# Connecteur_Nucleo.net
KiCad netlist of a schematic drawn in Altium Designer
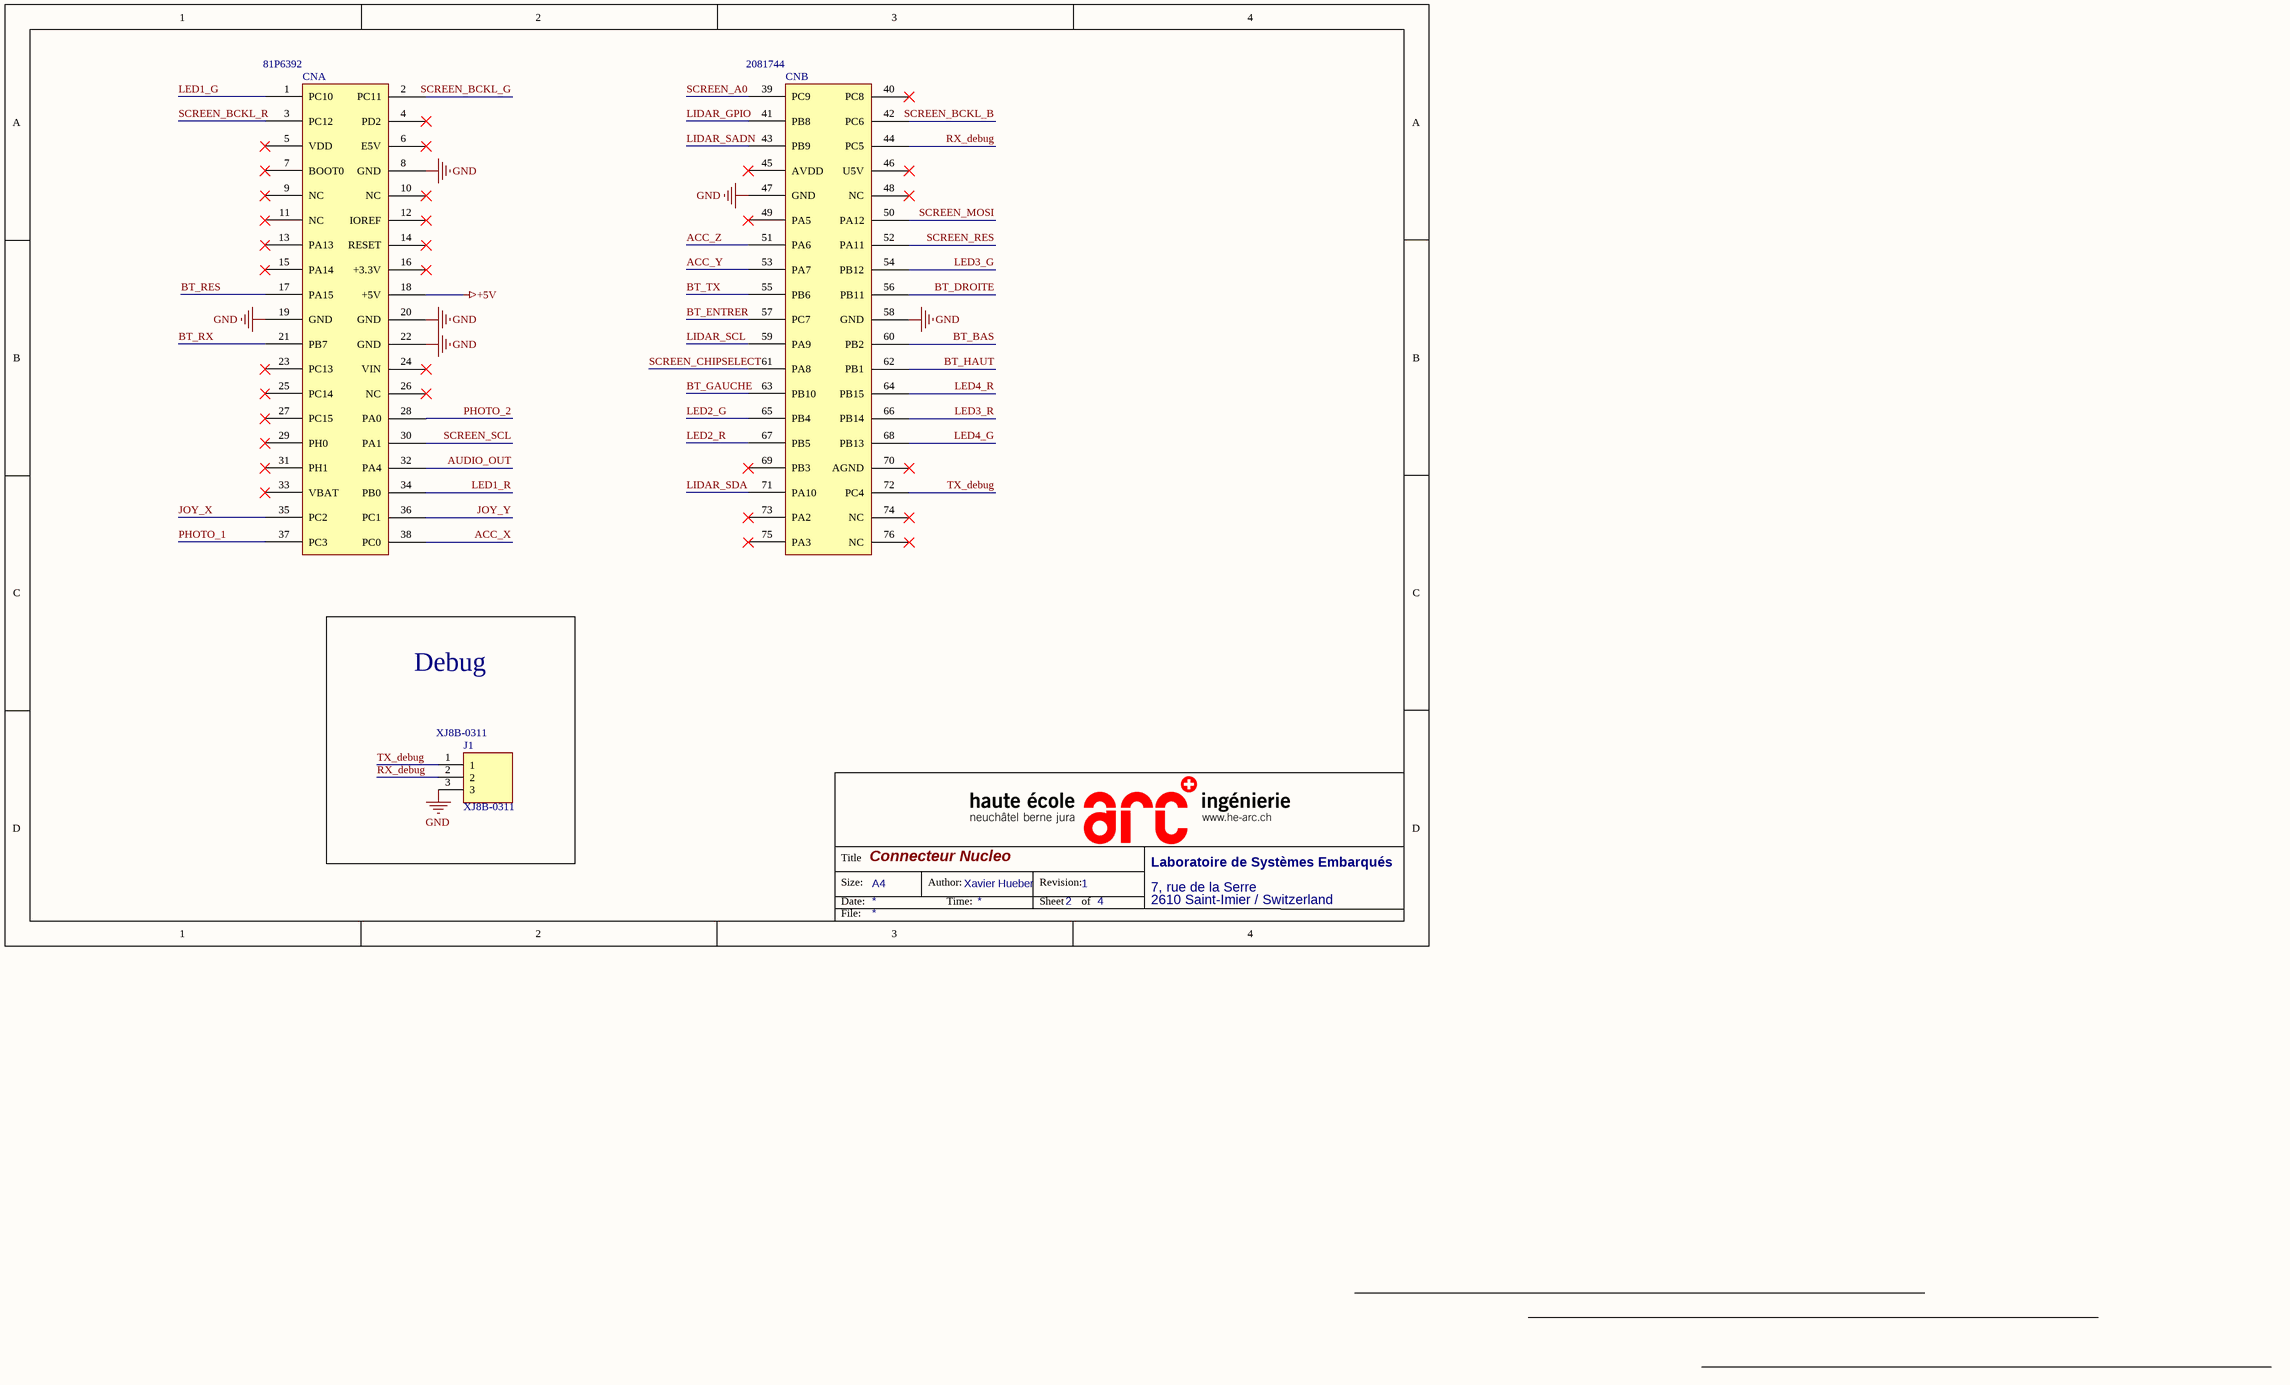
[diagram p0: Connecteur_Nucleo.SchDoc]

(export (version "E")
  (design (tool "Eeschema 10.0.6"))
  (components
    (comp (ref "CN")
      (value "~")
      (footprint "Nucleo-conn-SMD - sans 3D")
      (description "Headers & Wire Housings Surface Mount PCB Socket Strips, 0.100 pitch")
      (fields (field (name "SUPPLIER PART NUMBER 1") "81P6392"))
      (libsource (lib "MesComposants") (part "CN1"))
    )
    (comp (ref "J1")
      (value "XJ8B-0311")
      (footprint "SamacSys:HDRV3W64P0X254_1X3_760X250X580P")
      (description "Conn Unshrouded Header PL 3 POS 2.54mm Solder ST Top Entry Thru-Hole")
      (fields (field (name "SUPPLIER PART NUMBER 1") "XJ8B-0311"))
      (libsource (lib "*") (part "XJ8B-0311"))
    )
  )
  (nets
    (net (code "1") (name "+5V") (class "Default")
      (node (ref "CN") (pin "18") (pinfunction "+5V_18") (pintype "passive"))
    )
    (net (code "2") (name "/ACC_X") (class "Default")
      (node (ref "CN") (pin "38") (pinfunction "PC0_38") (pintype "passive"))
    )
    (net (code "3") (name "/ACC_Y") (class "Default")
      (node (ref "CN") (pin "53") (pinfunction "PA7_53") (pintype "passive"))
    )
    (net (code "4") (name "/ACC_Z") (class "Default")
      (node (ref "CN") (pin "51") (pinfunction "PA6_51") (pintype "passive"))
    )
    (net (code "5") (name "/AUDIO_OUT") (class "Default")
      (node (ref "CN") (pin "32") (pinfunction "PA4_32") (pintype "passive"))
    )
    (net (code "6") (name "/BT_BAS") (class "Default")
      (node (ref "CN") (pin "60") (pinfunction "PB2_60") (pintype "passive"))
    )
    (net (code "7") (name "/BT_DROITE") (class "Default")
      (node (ref "CN") (pin "56") (pinfunction "PB11_56") (pintype "passive"))
    )
    (net (code "8") (name "/BT_ENTRER") (class "Default")
      (node (ref "CN") (pin "57") (pinfunction "PC7_57") (pintype "passive"))
    )
    (net (code "9") (name "/BT_GAUCHE") (class "Default")
      (node (ref "CN") (pin "63") (pinfunction "PB10_63") (pintype "passive"))
    )
    (net (code "10") (name "/BT_HAUT") (class "Default")
      (node (ref "CN") (pin "62") (pinfunction "PB1_62") (pintype "passive"))
    )
    (net (code "11") (name "/BT_RES") (class "Default")
      (node (ref "CN") (pin "17") (pinfunction "PA15_17") (pintype "passive"))
    )
    (net (code "12") (name "/BT_RX") (class "Default")
      (node (ref "CN") (pin "21") (pinfunction "PB7_21") (pintype "passive"))
    )
    (net (code "13") (name "/BT_TX") (class "Default")
      (node (ref "CN") (pin "55") (pinfunction "PB6_55") (pintype "passive"))
    )
    (net (code "14") (name "/JOY_X") (class "Default")
      (node (ref "CN") (pin "35") (pinfunction "PC2_35") (pintype "passive"))
    )
    (net (code "15") (name "/JOY_Y") (class "Default")
      (node (ref "CN") (pin "36") (pinfunction "PC1_36") (pintype "passive"))
    )
    (net (code "16") (name "/LED1_G") (class "Default")
      (node (ref "CN") (pin "1") (pinfunction "PC10_1") (pintype "passive"))
    )
    (net (code "17") (name "/LED1_R") (class "Default")
      (node (ref "CN") (pin "34") (pinfunction "PB0_34") (pintype "passive"))
    )
    (net (code "18") (name "/LED2_G") (class "Default")
      (node (ref "CN") (pin "65") (pinfunction "PB4_65") (pintype "passive"))
    )
    (net (code "19") (name "/LED2_R") (class "Default")
      (node (ref "CN") (pin "67") (pinfunction "PB5_67") (pintype "passive"))
    )
    (net (code "20") (name "/LED3_G") (class "Default")
      (node (ref "CN") (pin "54") (pinfunction "PB12_54") (pintype "passive"))
    )
    (net (code "21") (name "/LED3_R") (class "Default")
      (node (ref "CN") (pin "66") (pinfunction "PB14_66") (pintype "passive"))
    )
    (net (code "22") (name "/LED4_G") (class "Default")
      (node (ref "CN") (pin "68") (pinfunction "PB13_68") (pintype "passive"))
    )
    (net (code "23") (name "/LED4_R") (class "Default")
      (node (ref "CN") (pin "64") (pinfunction "PB15_64") (pintype "passive"))
    )
    (net (code "24") (name "/LIDAR_GPIO") (class "Default")
      (node (ref "CN") (pin "41") (pinfunction "PB8_41") (pintype "passive"))
    )
    (net (code "25") (name "/LIDAR_SADN") (class "Default")
      (node (ref "CN") (pin "43") (pinfunction "PB9_43") (pintype "passive"))
    )
    (net (code "26") (name "/LIDAR_SCL") (class "Default")
      (node (ref "CN") (pin "59") (pinfunction "PA9_59") (pintype "passive"))
    )
    (net (code "27") (name "/LIDAR_SDA") (class "Default")
      (node (ref "CN") (pin "71") (pinfunction "PA10_71") (pintype "passive"))
    )
    (net (code "28") (name "/PHOTO_1") (class "Default")
      (node (ref "CN") (pin "37") (pinfunction "PC3_37") (pintype "passive"))
    )
    (net (code "29") (name "/PHOTO_2") (class "Default")
      (node (ref "CN") (pin "28") (pinfunction "PA0_28") (pintype "passive"))
    )
    (net (code "30") (name "/RX_debug") (class "Default")
      (node (ref "CN") (pin "44") (pinfunction "PC5_44") (pintype "passive"))
      (node (ref "J1") (pin "2") (pinfunction "2_2") (pintype "passive"))
    )
    (net (code "31") (name "/SCREEN_A0") (class "Default")
      (node (ref "CN") (pin "39") (pinfunction "PC9_39") (pintype "passive"))
    )
    (net (code "32") (name "/SCREEN_BCKL_B") (class "Default")
      (node (ref "CN") (pin "42") (pinfunction "PC6_42") (pintype "passive"))
    )
    (net (code "33") (name "/SCREEN_BCKL_G") (class "Default")
      (node (ref "CN") (pin "2") (pinfunction "PC11_2") (pintype "passive"))
    )
    (net (code "34") (name "/SCREEN_BCKL_R") (class "Default")
      (node (ref "CN") (pin "3") (pinfunction "PC12_3") (pintype "passive"))
    )
    (net (code "35") (name "/SCREEN_CHIPSELECT") (class "Default")
      (node (ref "CN") (pin "61") (pinfunction "PA8_61") (pintype "passive"))
    )
    (net (code "36") (name "/SCREEN_MOSI") (class "Default")
      (node (ref "CN") (pin "50") (pinfunction "PA12_50") (pintype "passive"))
    )
    (net (code "37") (name "/SCREEN_RES") (class "Default")
      (node (ref "CN") (pin "52") (pinfunction "PA11_52") (pintype "passive"))
    )
    (net (code "38") (name "/SCREEN_SCL") (class "Default")
      (node (ref "CN") (pin "30") (pinfunction "PA1_30") (pintype "passive"))
    )
    (net (code "39") (name "/TX_debug") (class "Default")
      (node (ref "CN") (pin "72") (pinfunction "PC4_72") (pintype "passive"))
      (node (ref "J1") (pin "1") (pinfunction "1_1") (pintype "passive"))
    )
    (net (code "40") (name "GND") (class "Default")
      (node (ref "CN") (pin "19") (pinfunction "GND_19") (pintype "passive"))
      (node (ref "CN") (pin "20") (pinfunction "GND_20") (pintype "passive"))
      (node (ref "CN") (pin "22") (pinfunction "GND_22") (pintype "passive"))
      (node (ref "CN") (pin "47") (pinfunction "GND_47") (pintype "passive"))
      (node (ref "CN") (pin "58") (pinfunction "GND_58") (pintype "passive"))
      (node (ref "CN") (pin "8") (pinfunction "GND_8") (pintype "passive"))
      (node (ref "J1") (pin "3") (pinfunction "3_3") (pintype "passive"))
    )
    (net (code "41") (name "unconnected-(CNA-+3.3V-Pad16)") (class "Default")
      (node (ref "CN") (pin "16") (pinfunction "+3.3V_16") (pintype "passive+no_connect"))
    )
    (net (code "42") (name "unconnected-(CNA-BOOT0-Pad7)") (class "Default")
      (node (ref "CN") (pin "7") (pinfunction "BOOT0_7") (pintype "passive+no_connect"))
    )
    (net (code "43") (name "unconnected-(CNA-E5V-Pad6)") (class "Default")
      (node (ref "CN") (pin "6") (pinfunction "E5V_6") (pintype "passive+no_connect"))
    )
    (net (code "44") (name "unconnected-(CNA-IOREF-Pad12)") (class "Default")
      (node (ref "CN") (pin "12") (pinfunction "IOREF_12") (pintype "passive+no_connect"))
    )
    (net (code "45") (name "unconnected-(CNA-NC-Pad9)") (class "Default")
      (node (ref "CN") (pin "9") (pinfunction "NC_9") (pintype "passive+no_connect"))
    )
    (net (code "46") (name "unconnected-(CNA-NC-Pad10)") (class "Default")
      (node (ref "CN") (pin "10") (pinfunction "NC_10") (pintype "passive+no_connect"))
    )
    (net (code "47") (name "unconnected-(CNA-NC-Pad11)") (class "Default")
      (node (ref "CN") (pin "11") (pinfunction "NC_11") (pintype "passive+no_connect"))
    )
    (net (code "48") (name "unconnected-(CNA-NC-Pad26)") (class "Default")
      (node (ref "CN") (pin "26") (pinfunction "NC_26") (pintype "passive+no_connect"))
    )
    (net (code "49") (name "unconnected-(CNA-PA13-Pad13)") (class "Default")
      (node (ref "CN") (pin "13") (pinfunction "PA13_13") (pintype "passive+no_connect"))
    )
    (net (code "50") (name "unconnected-(CNA-PA14-Pad15)") (class "Default")
      (node (ref "CN") (pin "15") (pinfunction "PA14_15") (pintype "passive+no_connect"))
    )
    (net (code "51") (name "unconnected-(CNA-PC13-Pad23)") (class "Default")
      (node (ref "CN") (pin "23") (pinfunction "PC13_23") (pintype "passive+no_connect"))
    )
    (net (code "52") (name "unconnected-(CNA-PC14-Pad25)") (class "Default")
      (node (ref "CN") (pin "25") (pinfunction "PC14_25") (pintype "passive+no_connect"))
    )
    (net (code "53") (name "unconnected-(CNA-PC15-Pad27)") (class "Default")
      (node (ref "CN") (pin "27") (pinfunction "PC15_27") (pintype "passive+no_connect"))
    )
    (net (code "54") (name "unconnected-(CNA-PD2-Pad4)") (class "Default")
      (node (ref "CN") (pin "4") (pinfunction "PD2_4") (pintype "passive+no_connect"))
    )
    (net (code "55") (name "unconnected-(CNA-PH0-Pad29)") (class "Default")
      (node (ref "CN") (pin "29") (pinfunction "PH0_29") (pintype "passive+no_connect"))
    )
    (net (code "56") (name "unconnected-(CNA-PH1-Pad31)") (class "Default")
      (node (ref "CN") (pin "31") (pinfunction "PH1_31") (pintype "passive+no_connect"))
    )
    (net (code "57") (name "unconnected-(CNA-RESET-Pad14)") (class "Default")
      (node (ref "CN") (pin "14") (pinfunction "RESET_14") (pintype "passive+no_connect"))
    )
    (net (code "58") (name "unconnected-(CNA-VBAT-Pad33)") (class "Default")
      (node (ref "CN") (pin "33") (pinfunction "VBAT_33") (pintype "passive+no_connect"))
    )
    (net (code "59") (name "unconnected-(CNA-VDD-Pad5)") (class "Default")
      (node (ref "CN") (pin "5") (pinfunction "VDD_5") (pintype "passive+no_connect"))
    )
    (net (code "60") (name "unconnected-(CNA-VIN-Pad24)") (class "Default")
      (node (ref "CN") (pin "24") (pinfunction "VIN_24") (pintype "passive+no_connect"))
    )
    (net (code "61") (name "unconnected-(CNB-AGND-Pad70)") (class "Default")
      (node (ref "CN") (pin "70") (pinfunction "AGND_70") (pintype "passive+no_connect"))
    )
    (net (code "62") (name "unconnected-(CNB-AVDD-Pad45)") (class "Default")
      (node (ref "CN") (pin "45") (pinfunction "AVDD_45") (pintype "passive+no_connect"))
    )
    (net (code "63") (name "unconnected-(CNB-NC-Pad48)") (class "Default")
      (node (ref "CN") (pin "48") (pinfunction "NC_48") (pintype "passive+no_connect"))
    )
    (net (code "64") (name "unconnected-(CNB-NC-Pad74)") (class "Default")
      (node (ref "CN") (pin "74") (pinfunction "NC_74") (pintype "passive+no_connect"))
    )
    (net (code "65") (name "unconnected-(CNB-NC-Pad76)") (class "Default")
      (node (ref "CN") (pin "76") (pinfunction "NC_76") (pintype "passive+no_connect"))
    )
    (net (code "66") (name "unconnected-(CNB-PA2-Pad73)") (class "Default")
      (node (ref "CN") (pin "73") (pinfunction "PA2_73") (pintype "passive+no_connect"))
    )
    (net (code "67") (name "unconnected-(CNB-PA3-Pad75)") (class "Default")
      (node (ref "CN") (pin "75") (pinfunction "PA3_75") (pintype "passive+no_connect"))
    )
    (net (code "68") (name "unconnected-(CNB-PA5-Pad49)") (class "Default")
      (node (ref "CN") (pin "49") (pinfunction "PA5_49") (pintype "passive+no_connect"))
    )
    (net (code "69") (name "unconnected-(CNB-PB3-Pad69)") (class "Default")
      (node (ref "CN") (pin "69") (pinfunction "PB3_69") (pintype "passive+no_connect"))
    )
    (net (code "70") (name "unconnected-(CNB-PC8-Pad40)") (class "Default")
      (node (ref "CN") (pin "40") (pinfunction "PC8_40") (pintype "passive+no_connect"))
    )
    (net (code "71") (name "unconnected-(CNB-U5V-Pad46)") (class "Default")
      (node (ref "CN") (pin "46") (pinfunction "U5V_46") (pintype "passive+no_connect"))
    )
  )
)
